# Sheet1.net
KiCad netlist of a schematic drawn in Altium Designer
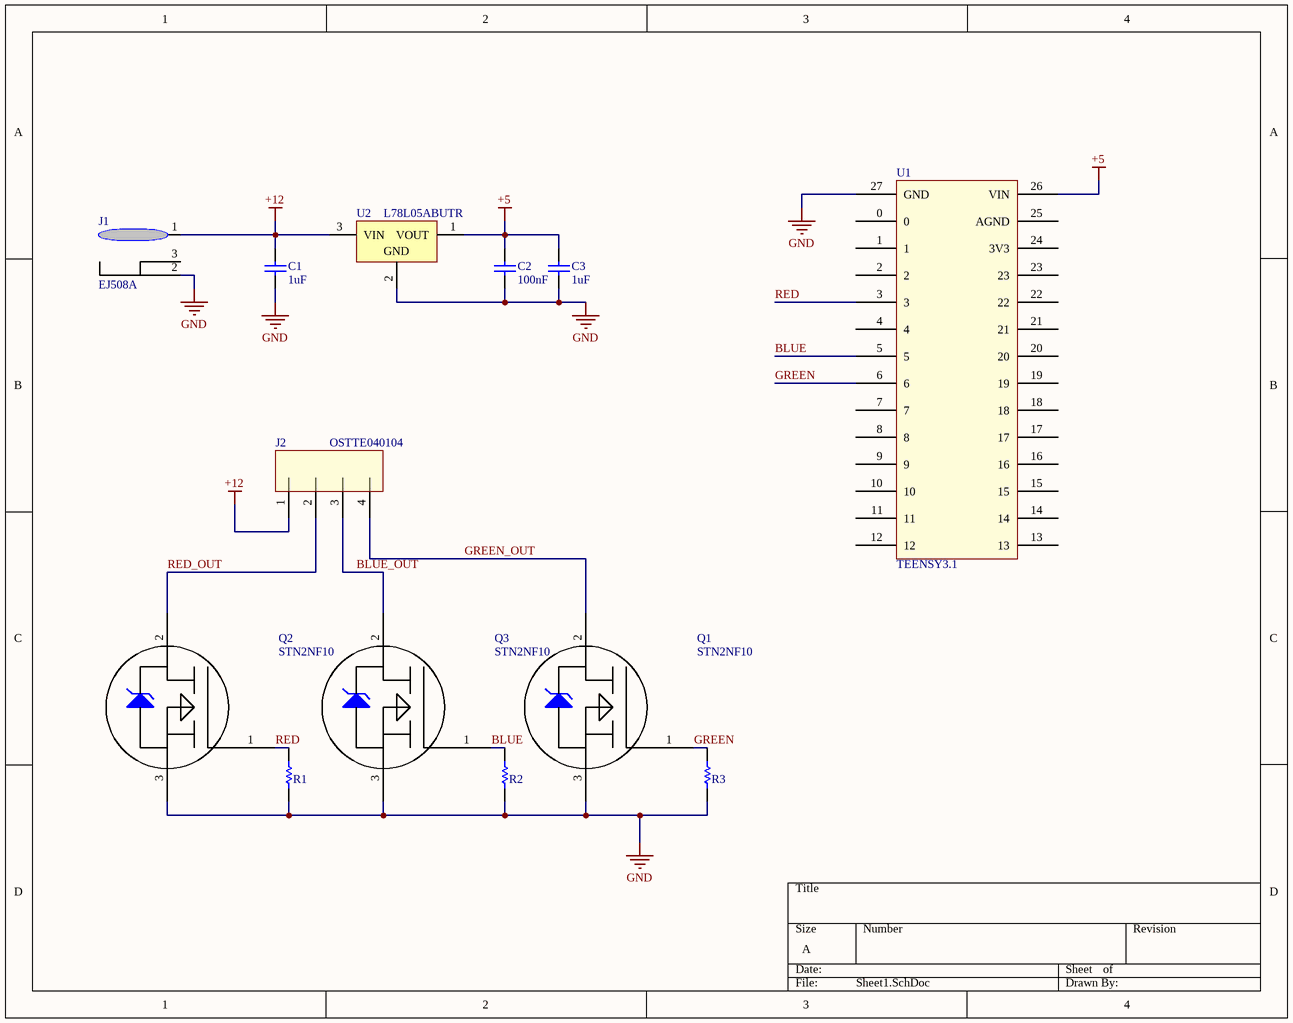
[diagram p0: Sheet1.SchDoc]

(export (version "E")
  (design (tool "Eeschema 10.0.6"))
  (components
    (comp (ref "C1")
      (value "1uF")
      (footprint "CAPC0805(2012)100_L")
      (description "CAP 1uF 25V ±10% 0805 (2012 Metric) Thickness 1mm SMD")
      (fields (field (name "TOLERANCE") "Â±10%"))
      (libsource (lib "Altium Content Vault") (part "CMP-1036-04754-1"))
    )
    (comp (ref "C2")
      (value "100nF")
      (footprint "CAPC0402(1005)60_N")
      (description "CAP 100nF 16V ±20% 0402 (1005 Metric) Thickness 0.6mm SMD")
      (fields (field (name "TOLERANCE") "Â±20%"))
      (libsource (lib "Altium Content Vault") (part "CMP-1034-02070-1"))
    )
    (comp (ref "C3")
      (value "1uF")
      (footprint "CAPC0805(2012)100_L")
      (description "CAP 1uF 16V ±10% 0805 (2012 Metric) Thickness 1mm SMD")
      (fields (field (name "TOLERANCE") "Â±10%"))
      (libsource (lib "Altium Content Vault") (part "CMP-1036-04754-1"))
    )
    (comp (ref "J1")
      (value "EJ508A")
      (footprint "2.1MM JACK")
      (description "Power Barrel Connector Jack 2.10mm ID (0.083\"), 5.50mm OD (0.217\") Through Hole, Right Angle")
      (fields (field (name "MANUFACTURER") "Memory Protection Devices"))
      (libsource (lib "Schlib1") (part "EJ508A"))
    )
    (comp (ref "J2")
      (value "OSTTE040104")
      (footprint "OSTTE040104")
      (description "TERMINAL BLOCK 3.5MM 4POS PCB")
      (libsource (lib "Schlib1") (part "OSTTE040104"))
    )
    (comp (ref "Q1")
      (value "STN2NF10")
      (footprint "SOT-223")
      (description "MOSFET N-CH 100V 2.4A SOT-223")
      (libsource (lib "Schlib1") (part "STN2NF10"))
    )
    (comp (ref "Q2")
      (value "STN2NF10")
      (footprint "SOT-223")
      (description "MOSFET N-CH 100V 2.4A SOT-223")
      (libsource (lib "Schlib1") (part "STN2NF10"))
    )
    (comp (ref "Q3")
      (value "STN2NF10")
      (footprint "SOT-223")
      (description "MOSFET N-CH 100V 2.4A SOT-223")
      (libsource (lib "Schlib1") (part "STN2NF10"))
    )
    (comp (ref "R1")
      (value "100K 5% 0402(1005)")
      (footprint "RESC0402(1005)_M")
      (description "100K 0.063W 5% 0402 (1005 Metric)  SMD")
      (fields (field (name "POWER") "0.063 W") (field (name "TOLERANCE") "5 %"))
      (libsource (lib "Altium Content Vault") (part "RES"))
    )
    (comp (ref "R2")
      (value "100K 5% 0402(1005)")
      (footprint "RESC0402(1005)_M")
      (description "100K 0.063W 5% 0402 (1005 Metric)  SMD")
      (fields (field (name "POWER") "0.063 W") (field (name "TOLERANCE") "5 %"))
      (libsource (lib "Altium Content Vault") (part "RES"))
    )
    (comp (ref "R3")
      (value "100K 5% 0402(1005)")
      (footprint "RESC0402(1005)_M")
      (description "100K 0.063W 5% 0402 (1005 Metric)  SMD")
      (fields (field (name "POWER") "0.063 W") (field (name "TOLERANCE") "5 %"))
      (libsource (lib "Altium Content Vault") (part "RES"))
    )
    (comp (ref "U1")
      (value "TEENSY3.1")
      (footprint "TEENSY3.1")
      (libsource (lib "Schlib1") (part "TEENSY3.1"))
    )
    (comp (ref "U2")
      (value "L78L05ABUTR")
      (footprint "SOT-89_M")
      (description "Positive Voltage Regulator, 5V, 4-Pin SOT-89, Tape and Reel")
      (libsource (lib "Altium Content Vault") (part "PM-REG-7805-SIL3"))
    )
  )
  (nets
    (net (code "1") (name "+5") (class "Default")
      (node (ref "C2") (pin "2") (pinfunction "2_2") (pintype "passive"))
      (node (ref "C3") (pin "2") (pinfunction "2_2") (pintype "passive"))
      (node (ref "U1") (pin "26") (pinfunction "VIN_26") (pintype "passive"))
      (node (ref "U2") (pin "1") (pinfunction "VOUT_1") (pintype "power_in"))
    )
    (net (code "2") (name "+12") (class "Default")
      (node (ref "C1") (pin "2") (pinfunction "2_2") (pintype "passive"))
      (node (ref "J1") (pin "1") (pintype "power_in"))
      (node (ref "U2") (pin "3") (pinfunction "VIN_3") (pintype "power_in"))
    )
    (net (code "3") (name "/BLUE") (class "Default")
      (node (ref "Q3") (pin "1") (pinfunction "G_1") (pintype "passive"))
      (node (ref "R2") (pin "2") (pinfunction "2_2") (pintype "passive"))
      (node (ref "U1") (pin "5") (pinfunction "5_5") (pintype "passive"))
    )
    (net (code "4") (name "/BLUE_OUT") (class "Default")
      (node (ref "Q3") (pin "2") (pinfunction "D_2") (pintype "passive"))
    )
    (net (code "5") (name "/GREEN") (class "Default")
      (node (ref "Q1") (pin "1") (pinfunction "G_1") (pintype "passive"))
      (node (ref "R3") (pin "2") (pinfunction "2_2") (pintype "passive"))
      (node (ref "U1") (pin "6") (pinfunction "6_6") (pintype "passive"))
    )
    (net (code "6") (name "/GREEN_OUT") (class "Default")
      (node (ref "Q1") (pin "2") (pinfunction "D_2") (pintype "passive"))
    )
    (net (code "7") (name "/RED") (class "Default")
      (node (ref "Q2") (pin "1") (pinfunction "G_1") (pintype "passive"))
      (node (ref "R1") (pin "2") (pinfunction "2_2") (pintype "passive"))
      (node (ref "U1") (pin "3") (pinfunction "3_3") (pintype "passive"))
    )
    (net (code "8") (name "/RED_OUT") (class "Default")
      (node (ref "Q2") (pin "2") (pinfunction "D_2") (pintype "passive"))
    )
    (net (code "9") (name "GND") (class "Default")
      (node (ref "C1") (pin "1") (pinfunction "1_1") (pintype "passive"))
      (node (ref "C2") (pin "1") (pinfunction "1_1") (pintype "passive"))
      (node (ref "C3") (pin "1") (pinfunction "1_1") (pintype "passive"))
      (node (ref "J1") (pin "2") (pintype "power_in"))
      (node (ref "Q1") (pin "3") (pinfunction "S_3") (pintype "passive"))
      (node (ref "Q2") (pin "3") (pinfunction "S_3") (pintype "passive"))
      (node (ref "Q3") (pin "3") (pinfunction "S_3") (pintype "passive"))
      (node (ref "R1") (pin "1") (pinfunction "1_1") (pintype "passive"))
      (node (ref "R2") (pin "1") (pinfunction "1_1") (pintype "passive"))
      (node (ref "R3") (pin "1") (pinfunction "1_1") (pintype "passive"))
      (node (ref "U1") (pin "27") (pinfunction "GND_27") (pintype "passive"))
      (node (ref "U2") (pin "2") (pinfunction "GND_2") (pintype "power_in"))
    )
    (net (code "10") (name "unconnected-(J1-Pad3)") (class "Default")
      (node (ref "J1") (pin "3") (pintype "power_in"))
    )
    (net (code "11") (name "unconnected-(J2-Pad1)") (class "Default")
      (node (ref "J2") (pin "1") (pintype "passive"))
    )
    (net (code "12") (name "unconnected-(J2-Pad2)") (class "Default")
      (node (ref "J2") (pin "2") (pintype "passive"))
    )
    (net (code "13") (name "unconnected-(J2-Pad3)") (class "Default")
      (node (ref "J2") (pin "3") (pintype "passive"))
    )
    (net (code "14") (name "unconnected-(J2-Pad4)") (class "Default")
      (node (ref "J2") (pin "4") (pintype "passive"))
    )
    (net (code "15") (name "unconnected-(U1-3V3-Pad24)") (class "Default")
      (node (ref "U1") (pin "24") (pinfunction "3V3_24") (pintype "passive"))
    )
    (net (code "16") (name "unconnected-(U1-AGND-Pad25)") (class "Default")
      (node (ref "U1") (pin "25") (pinfunction "AGND_25") (pintype "passive"))
    )
    (net (code "17") (name "unconnected-(U1-Pad0)") (class "Default")
      (node (ref "U1") (pin "0") (pinfunction "0_0") (pintype "passive"))
    )
    (net (code "18") (name "unconnected-(U1-Pad1)") (class "Default")
      (node (ref "U1") (pin "1") (pinfunction "1_1") (pintype "passive"))
    )
    (net (code "19") (name "unconnected-(U1-Pad2)") (class "Default")
      (node (ref "U1") (pin "2") (pinfunction "2_2") (pintype "passive"))
    )
    (net (code "20") (name "unconnected-(U1-Pad4)") (class "Default")
      (node (ref "U1") (pin "4") (pinfunction "4_4") (pintype "passive"))
    )
    (net (code "21") (name "unconnected-(U1-Pad7)") (class "Default")
      (node (ref "U1") (pin "7") (pinfunction "7_7") (pintype "passive"))
    )
    (net (code "22") (name "unconnected-(U1-Pad8)") (class "Default")
      (node (ref "U1") (pin "8") (pinfunction "8_8") (pintype "passive"))
    )
    (net (code "23") (name "unconnected-(U1-Pad9)") (class "Default")
      (node (ref "U1") (pin "9") (pinfunction "9_9") (pintype "passive"))
    )
    (net (code "24") (name "unconnected-(U1-Pad10)") (class "Default")
      (node (ref "U1") (pin "10") (pinfunction "10_10") (pintype "passive"))
    )
    (net (code "25") (name "unconnected-(U1-Pad11)") (class "Default")
      (node (ref "U1") (pin "11") (pinfunction "11_11") (pintype "passive"))
    )
    (net (code "26") (name "unconnected-(U1-Pad12)") (class "Default")
      (node (ref "U1") (pin "12") (pinfunction "12_12") (pintype "passive"))
    )
    (net (code "27") (name "unconnected-(U1-Pad13)") (class "Default")
      (node (ref "U1") (pin "13") (pinfunction "13_13") (pintype "passive"))
    )
    (net (code "28") (name "unconnected-(U1-Pad14)") (class "Default")
      (node (ref "U1") (pin "14") (pinfunction "14_14") (pintype "passive"))
    )
    (net (code "29") (name "unconnected-(U1-Pad15)") (class "Default")
      (node (ref "U1") (pin "15") (pinfunction "15_15") (pintype "passive"))
    )
    (net (code "30") (name "unconnected-(U1-Pad16)") (class "Default")
      (node (ref "U1") (pin "16") (pinfunction "16_16") (pintype "passive"))
    )
    (net (code "31") (name "unconnected-(U1-Pad17)") (class "Default")
      (node (ref "U1") (pin "17") (pinfunction "17_17") (pintype "passive"))
    )
    (net (code "32") (name "unconnected-(U1-Pad18)") (class "Default")
      (node (ref "U1") (pin "18") (pinfunction "18_18") (pintype "passive"))
    )
    (net (code "33") (name "unconnected-(U1-Pad19)") (class "Default")
      (node (ref "U1") (pin "19") (pinfunction "19_19") (pintype "passive"))
    )
    (net (code "34") (name "unconnected-(U1-Pad20)") (class "Default")
      (node (ref "U1") (pin "20") (pinfunction "20_20") (pintype "passive"))
    )
    (net (code "35") (name "unconnected-(U1-Pad21)") (class "Default")
      (node (ref "U1") (pin "21") (pinfunction "21_21") (pintype "passive"))
    )
    (net (code "36") (name "unconnected-(U1-Pad22)") (class "Default")
      (node (ref "U1") (pin "22") (pinfunction "22_22") (pintype "passive"))
    )
    (net (code "37") (name "unconnected-(U1-Pad23)") (class "Default")
      (node (ref "U1") (pin "23") (pinfunction "23_23") (pintype "passive"))
    )
  )
)
